# Audio_module.net
KiCad netlist of a schematic drawn in Altium Designer
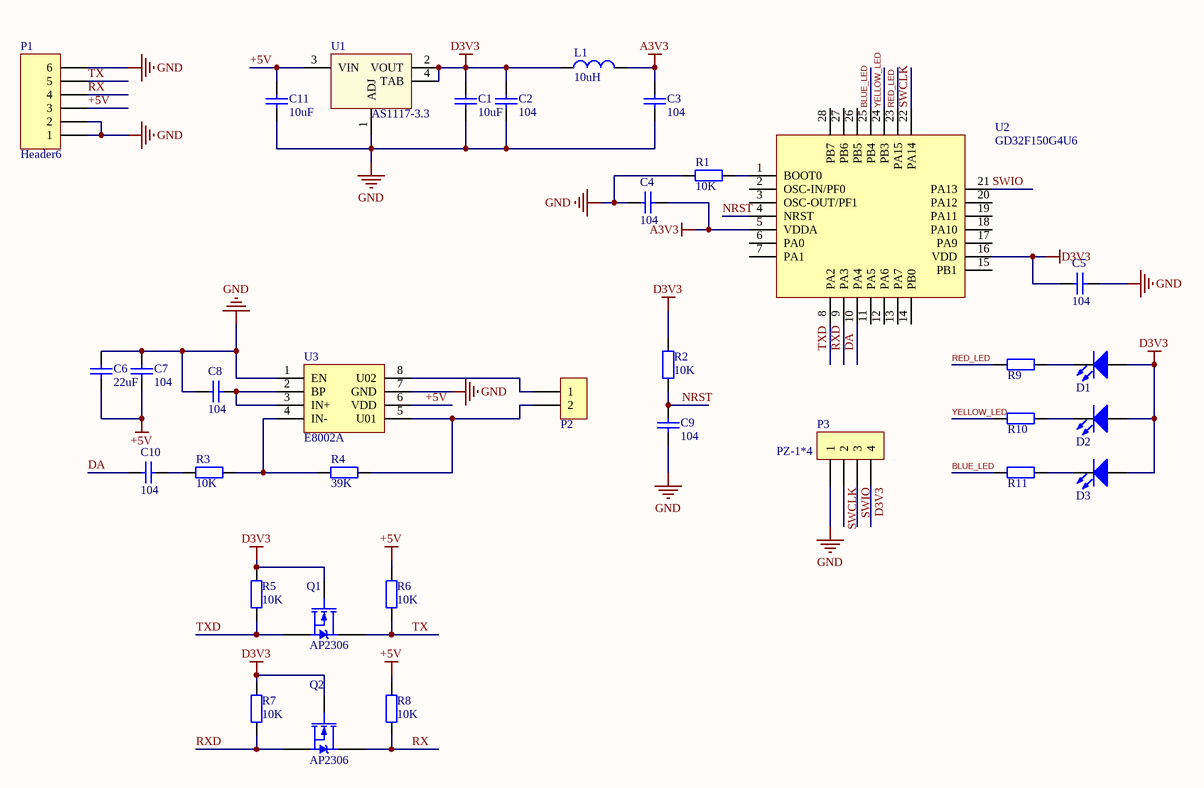
[diagram p0: Audio module.SchDoc]

(export (version "E")
  (design (tool "Eeschema 10.0.6"))
  (components
    (comp (ref "C1")
      (value "10uF")
      (footprint "0603-2")
      (description "无极性电容")
      (fields (field (name "Comment") "Cap") (field (name "PUBLISHER") "Altium Limited"))
      (libsource (lib "Audio module") (part "Cap"))
    )
    (comp (ref "C2")
      (value "104")
      (footprint "0603-2")
      (description "无极性电容")
      (fields (field (name "Comment") "Cap") (field (name "PUBLISHER") "Altium Limited"))
      (libsource (lib "Audio module") (part "Cap"))
    )
    (comp (ref "C3")
      (value "104")
      (footprint "0603-2")
      (description "无极性电容")
      (fields (field (name "Comment") "Cap") (field (name "PUBLISHER") "Altium Limited"))
      (libsource (lib "Audio module") (part "Cap"))
    )
    (comp (ref "C4")
      (value "104")
      (footprint "0603-2")
      (description "无极性电容")
      (fields (field (name "Comment") "Cap") (field (name "PUBLISHER") "Altium Limited"))
      (libsource (lib "Audio module") (part "Cap"))
    )
    (comp (ref "C5")
      (value "104")
      (footprint "0603-2")
      (description "无极性电容")
      (fields (field (name "Comment") "Cap") (field (name "PUBLISHER") "Altium Limited"))
      (libsource (lib "Audio module") (part "Cap"))
    )
    (comp (ref "C6")
      (value "22uF")
      (footprint "0603-2")
      (description "无极性电容")
      (fields (field (name "Comment") "Cap") (field (name "PUBLISHER") "Altium Limited"))
      (libsource (lib "Audio module") (part "Cap"))
    )
    (comp (ref "C7")
      (value "104")
      (footprint "0603-2")
      (description "无极性电容")
      (fields (field (name "Comment") "Cap") (field (name "PUBLISHER") "Altium Limited"))
      (libsource (lib "Audio module") (part "Cap"))
    )
    (comp (ref "C8")
      (value "104")
      (footprint "0603-2")
      (description "无极性电容")
      (fields (field (name "Comment") "Cap") (field (name "PUBLISHER") "Altium Limited"))
      (libsource (lib "Audio module") (part "Cap"))
    )
    (comp (ref "C9")
      (value "104")
      (footprint "0603-2")
      (description "无极性电容")
      (fields (field (name "Comment") "Cap") (field (name "PUBLISHER") "Altium Limited"))
      (libsource (lib "Audio module") (part "Cap"))
    )
    (comp (ref "C10")
      (value "104")
      (footprint "0603-2")
      (description "无极性电容")
      (fields (field (name "Comment") "Cap") (field (name "PUBLISHER") "Altium Limited"))
      (libsource (lib "Audio module") (part "Cap"))
    )
    (comp (ref "C11")
      (value "10uF")
      (footprint "0603-2")
      (description "无极性电容")
      (fields (field (name "Comment") "Cap") (field (name "PUBLISHER") "Altium Limited"))
      (libsource (lib "Audio module") (part "Cap"))
    )
    (comp (ref "D1") (value "RED_LED") (footprint "RES_0603") (libsource (lib "zzk") (part "LED")))
    (comp (ref "D2") (value "YELLOW_LED") (footprint "RES_0603") (libsource (lib "zzk") (part "LED")))
    (comp (ref "D3") (value "BLUE_LED") (footprint "RES_0603") (libsource (lib "zzk") (part "LED")))
    (comp (ref "L1")
      (value "10uH")
      (footprint "0805-1")
      (description "电感")
      (fields (field (name "Comment") "Inductor") (field (name "PUBLISHER") "Altium Limited"))
      (libsource (lib "Audio module") (part "Inductor"))
    )
    (comp (ref "P1")
      (value "Header6")
      (footprint "HDR6X1_A")
      (libsource (lib "Audio module") (part "Header6"))
    )
    (comp (ref "P2") (value "PZ-1*2") (footprint "HDR2X1_A") (libsource (lib "Audio module") (part "PZ-1*2")))
    (comp (ref "P3") (value "PZ-1*4") (footprint "HDR4X1_A") (libsource (lib "Audio module") (part "PZ-1*4")))
    (comp (ref "Q1")
      (value "AP2306")
      (footprint "SOT-23")
      (description "N-MOSFET1")
      (fields (field (name "PUBLISHER") "Altium Limited"))
      (libsource (lib "Audio module") (part "MOSFET-N1"))
    )
    (comp (ref "Q2")
      (value "AP2306")
      (footprint "SOT-23")
      (description "N-MOSFET1")
      (fields (field (name "PUBLISHER") "Altium Limited"))
      (libsource (lib "Audio module") (part "MOSFET-N1"))
    )
    (comp (ref "R1")
      (value "10K")
      (footprint "RES-0603")
      (description "贴片电阻")
      (fields (field (name "PUBLISHER") "Altium Limited"))
      (libsource (lib "") (part "Res1_2"))
    )
    (comp (ref "R2")
      (value "10K")
      (footprint "RES-0603")
      (description "贴片电阻")
      (fields (field (name "PUBLISHER") "Altium Limited"))
      (libsource (lib "Audio module") (part "Res1"))
    )
    (comp (ref "R3")
      (value "10K")
      (footprint "0603-1")
      (description "贴片电阻")
      (fields (field (name "Comment") "Res1") (field (name "PUBLISHER") "Altium Limited"))
      (libsource (lib "") (part "Res1_1"))
    )
    (comp (ref "R4")
      (value "39K")
      (footprint "0603-1")
      (description "贴片电阻")
      (fields (field (name "Comment") "Res1") (field (name "PUBLISHER") "Altium Limited"))
      (libsource (lib "") (part "Res1_1"))
    )
    (comp (ref "R5")
      (value "10K")
      (footprint "RES-0603")
      (description "贴片电阻")
      (fields (field (name "PUBLISHER") "Altium Limited"))
      (libsource (lib "Audio module") (part "Res1"))
    )
    (comp (ref "R6")
      (value "10K")
      (footprint "RES-0603")
      (description "贴片电阻")
      (fields (field (name "PUBLISHER") "Altium Limited"))
      (libsource (lib "Audio module") (part "Res1"))
    )
    (comp (ref "R7")
      (value "10K")
      (footprint "RES-0603")
      (description "贴片电阻")
      (fields (field (name "PUBLISHER") "Altium Limited"))
      (libsource (lib "Audio module") (part "Res1"))
    )
    (comp (ref "R8")
      (value "10K")
      (footprint "RES-0603")
      (description "贴片电阻")
      (fields (field (name "PUBLISHER") "Altium Limited"))
      (libsource (lib "Audio module") (part "Res1"))
    )
    (comp (ref "R9") (value "RES") (footprint "RES_0603") (libsource (lib "zzk") (part "RES")))
    (comp (ref "R10") (value "RES") (footprint "RES_0603") (libsource (lib "zzk") (part "RES")))
    (comp (ref "R11") (value "RES") (footprint "RES_0603") (libsource (lib "zzk") (part "RES")))
    (comp (ref "U1")
      (value "AS1117-3.3")
      (footprint "SOT-223")
      (description "AS1117")
      (libsource (lib "Audio module") (part "AS1117"))
    )
    (comp (ref "U2")
      (value "GD32F150G4U6")
      (footprint "QFN28-1")
      (libsource (lib "Audio module") (part "GD32F150G4U6"))
    )
    (comp (ref "U3") (value "E8002A") (footprint "SOP-8") (libsource (lib "Audio module") (part "E8002A")))
  )
  (nets
    (net (code "1") (name "+5V") (class "Default")
      (node (ref "C11") (pin "2") (pinfunction "2_2") (pintype "passive"))
      (node (ref "C6") (pin "2") (pinfunction "2_2") (pintype "passive"))
      (node (ref "C7") (pin "1") (pinfunction "1_1") (pintype "passive"))
      (node (ref "P1") (pin "3") (pinfunction "3_3") (pintype "passive"))
      (node (ref "R6") (pin "2") (pinfunction "2_2") (pintype "passive"))
      (node (ref "R8") (pin "2") (pinfunction "2_2") (pintype "passive"))
      (node (ref "U1") (pin "3") (pinfunction "VIN_3") (pintype "passive"))
      (node (ref "U3") (pin "6") (pinfunction "VDD_6") (pintype "passive"))
    )
    (net (code "2") (name "/BLUE_LED") (class "Default")
      (node (ref "R11") (pin "1") (pinfunction "1_1") (pintype "passive"))
      (node (ref "U2") (pin "25") (pinfunction "PB4_25") (pintype "passive"))
    )
    (net (code "3") (name "/DA") (class "Default")
      (node (ref "C10") (pin "2") (pinfunction "2_2") (pintype "passive"))
      (node (ref "U2") (pin "10") (pinfunction "PA4_10") (pintype "passive"))
    )
    (net (code "4") (name "/NRST") (class "Default")
      (node (ref "C9") (pin "2") (pinfunction "2_2") (pintype "passive"))
      (node (ref "R2") (pin "1") (pinfunction "1_1") (pintype "passive"))
      (node (ref "U2") (pin "4") (pinfunction "NRST_4") (pintype "passive"))
    )
    (net (code "5") (name "/RED_LED") (class "Default")
      (node (ref "R9") (pin "1") (pinfunction "1_1") (pintype "passive"))
      (node (ref "U2") (pin "23") (pinfunction "PA15_23") (pintype "passive"))
    )
    (net (code "6") (name "/RX") (class "Default")
      (node (ref "P1") (pin "4") (pinfunction "4_4") (pintype "passive"))
      (node (ref "Q2") (pin "3") (pinfunction "D_3") (pintype "passive"))
      (node (ref "R8") (pin "1") (pinfunction "1_1") (pintype "passive"))
    )
    (net (code "7") (name "/RXD") (class "Default")
      (node (ref "Q2") (pin "2") (pinfunction "S_2") (pintype "passive"))
      (node (ref "R7") (pin "1") (pinfunction "1_1") (pintype "passive"))
      (node (ref "U2") (pin "9") (pinfunction "PA3_9") (pintype "passive"))
    )
    (net (code "8") (name "/SWCLK") (class "Default")
      (node (ref "P3") (pin "2") (pinfunction "2_2") (pintype "passive"))
      (node (ref "U2") (pin "22") (pinfunction "PA14_22") (pintype "passive"))
    )
    (net (code "9") (name "/SWIO") (class "Default")
      (node (ref "P3") (pin "3") (pinfunction "3_3") (pintype "passive"))
      (node (ref "U2") (pin "21") (pinfunction "PA13_21") (pintype "passive"))
    )
    (net (code "10") (name "/TX") (class "Default")
      (node (ref "P1") (pin "5") (pinfunction "5_5") (pintype "passive"))
      (node (ref "Q1") (pin "3") (pinfunction "D_3") (pintype "passive"))
      (node (ref "R6") (pin "1") (pinfunction "1_1") (pintype "passive"))
    )
    (net (code "11") (name "/TXD") (class "Default")
      (node (ref "Q1") (pin "2") (pinfunction "S_2") (pintype "passive"))
      (node (ref "R5") (pin "1") (pinfunction "1_1") (pintype "passive"))
      (node (ref "U2") (pin "8") (pinfunction "PA2_8") (pintype "passive"))
    )
    (net (code "12") (name "/YELLOW_LED") (class "Default")
      (node (ref "R10") (pin "1") (pinfunction "1_1") (pintype "passive"))
      (node (ref "U2") (pin "24") (pinfunction "PB3_24") (pintype "passive"))
    )
    (net (code "13") (name "A3V3") (class "Default")
      (node (ref "C3") (pin "2") (pinfunction "2_2") (pintype "passive"))
      (node (ref "C4") (pin "1") (pinfunction "1_1") (pintype "passive"))
      (node (ref "L1") (pin "2") (pinfunction "2_2") (pintype "passive"))
      (node (ref "U2") (pin "5") (pinfunction "VDDA_5") (pintype "passive"))
    )
    (net (code "14") (name "D3V3") (class "Default")
      (node (ref "C1") (pin "2") (pinfunction "2_2") (pintype "passive"))
      (node (ref "C2") (pin "2") (pinfunction "2_2") (pintype "passive"))
      (node (ref "C5") (pin "2") (pinfunction "2_2") (pintype "passive"))
      (node (ref "D1") (pin "1") (pinfunction "A_1") (pintype "passive"))
      (node (ref "D2") (pin "1") (pinfunction "A_1") (pintype "passive"))
      (node (ref "D3") (pin "1") (pinfunction "A_1") (pintype "passive"))
      (node (ref "L1") (pin "1") (pinfunction "1_1") (pintype "passive"))
      (node (ref "P3") (pin "4") (pinfunction "4_4") (pintype "passive"))
      (node (ref "R2") (pin "2") (pinfunction "2_2") (pintype "passive"))
      (node (ref "R5") (pin "2") (pinfunction "2_2") (pintype "passive"))
      (node (ref "R7") (pin "2") (pinfunction "2_2") (pintype "passive"))
      (node (ref "U1") (pin "2") (pinfunction "VOUT_2") (pintype "passive"))
      (node (ref "U1") (pin "4") (pinfunction "TAB_4") (pintype "passive"))
      (node (ref "U2") (pin "16") (pinfunction "VDD_16") (pintype "passive"))
    )
    (net (code "15") (name "GND") (class "Default")
      (node (ref "C1") (pin "1") (pinfunction "1_1") (pintype "passive"))
      (node (ref "C11") (pin "1") (pinfunction "1_1") (pintype "passive"))
      (node (ref "C2") (pin "1") (pinfunction "1_1") (pintype "passive"))
      (node (ref "C3") (pin "1") (pinfunction "1_1") (pintype "passive"))
      (node (ref "C4") (pin "2") (pinfunction "2_2") (pintype "passive"))
      (node (ref "C5") (pin "1") (pinfunction "1_1") (pintype "passive"))
      (node (ref "C6") (pin "1") (pinfunction "1_1") (pintype "passive"))
      (node (ref "C7") (pin "2") (pinfunction "2_2") (pintype "passive"))
      (node (ref "C8") (pin "2") (pinfunction "2_2") (pintype "passive"))
      (node (ref "C9") (pin "1") (pinfunction "1_1") (pintype "passive"))
      (node (ref "P1") (pin "1") (pinfunction "1_1") (pintype "passive"))
      (node (ref "P1") (pin "2") (pinfunction "2_2") (pintype "passive"))
      (node (ref "P1") (pin "6") (pinfunction "6_6") (pintype "passive"))
      (node (ref "P3") (pin "1") (pinfunction "1_1") (pintype "passive"))
      (node (ref "R1") (pin "2") (pinfunction "2_2") (pintype "passive"))
      (node (ref "U1") (pin "1") (pinfunction "ADJ_1") (pintype "passive"))
      (node (ref "U3") (pin "1") (pinfunction "EN_1") (pintype "passive"))
      (node (ref "U3") (pin "7") (pinfunction "GND_7") (pintype "passive"))
    )
    (net (code "16") (name "Net-(C10-Pad1)") (class "Default")
      (node (ref "C10") (pin "1") (pinfunction "1_1") (pintype "passive"))
      (node (ref "R3") (pin "1") (pinfunction "1_1") (pintype "passive"))
    )
    (net (code "17") (name "Net-(D1-K)") (class "Default")
      (node (ref "D1") (pin "2") (pinfunction "K_2") (pintype "passive"))
      (node (ref "R9") (pin "2") (pinfunction "2_2") (pintype "passive"))
    )
    (net (code "18") (name "Net-(D2-K)") (class "Default")
      (node (ref "D2") (pin "2") (pinfunction "K_2") (pintype "passive"))
      (node (ref "R10") (pin "2") (pinfunction "2_2") (pintype "passive"))
    )
    (net (code "19") (name "Net-(D3-K)") (class "Default")
      (node (ref "D3") (pin "2") (pinfunction "K_2") (pintype "passive"))
      (node (ref "R11") (pin "2") (pinfunction "2_2") (pintype "passive"))
    )
    (net (code "20") (name "Net-(U2-BOOT0)") (class "Default")
      (node (ref "R1") (pin "1") (pinfunction "1_1") (pintype "passive"))
      (node (ref "U2") (pin "1") (pinfunction "BOOT0_1") (pintype "passive"))
    )
    (net (code "21") (name "Net-(U3-BP)") (class "Default")
      (node (ref "C8") (pin "1") (pinfunction "1_1") (pintype "passive"))
      (node (ref "U3") (pin "2") (pinfunction "BP_2") (pintype "passive"))
      (node (ref "U3") (pin "3") (pinfunction "IN+_3") (pintype "passive"))
    )
    (net (code "22") (name "Net-(U3-IN-)") (class "Default")
      (node (ref "R3") (pin "2") (pinfunction "2_2") (pintype "passive"))
      (node (ref "R4") (pin "1") (pinfunction "1_1") (pintype "passive"))
      (node (ref "U3") (pin "4") (pinfunction "IN-_4") (pintype "passive"))
    )
    (net (code "23") (name "Net-(U3-U01)") (class "Default")
      (node (ref "P2") (pin "2") (pinfunction "2_2") (pintype "passive"))
      (node (ref "R4") (pin "2") (pinfunction "2_2") (pintype "passive"))
      (node (ref "U3") (pin "5") (pinfunction "U01_5") (pintype "passive"))
    )
    (net (code "24") (name "Net-(U3-U02)") (class "Default")
      (node (ref "P2") (pin "1") (pinfunction "1_1") (pintype "passive"))
      (node (ref "U3") (pin "8") (pinfunction "U02_8") (pintype "passive"))
    )
    (net (code "25") (name "unconnected-(Q1-1-PadG)") (class "Default")
      (node (ref "Q1") (pin "G") (pinfunction "1_G") (pintype "passive"))
    )
    (net (code "26") (name "unconnected-(Q2-1-PadG)") (class "Default")
      (node (ref "Q2") (pin "G") (pinfunction "1_G") (pintype "passive"))
    )
    (net (code "27") (name "unconnected-(U2-OSC-IN{slash}PF0-Pad2)") (class "Default")
      (node (ref "U2") (pin "2") (pinfunction "OSC-IN/PF0_2") (pintype "passive"))
    )
    (net (code "28") (name "unconnected-(U2-OSC-OUT{slash}PF1-Pad3)") (class "Default")
      (node (ref "U2") (pin "3") (pinfunction "OSC-OUT/PF1_3") (pintype "passive"))
    )
    (net (code "29") (name "unconnected-(U2-PA0-Pad6)") (class "Default")
      (node (ref "U2") (pin "6") (pinfunction "PA0_6") (pintype "passive"))
    )
    (net (code "30") (name "unconnected-(U2-PA1-Pad7)") (class "Default")
      (node (ref "U2") (pin "7") (pinfunction "PA1_7") (pintype "passive"))
    )
    (net (code "31") (name "unconnected-(U2-PA5-Pad11)") (class "Default")
      (node (ref "U2") (pin "11") (pinfunction "PA5_11") (pintype "passive"))
    )
    (net (code "32") (name "unconnected-(U2-PA6-Pad12)") (class "Default")
      (node (ref "U2") (pin "12") (pinfunction "PA6_12") (pintype "passive"))
    )
    (net (code "33") (name "unconnected-(U2-PA7-Pad13)") (class "Default")
      (node (ref "U2") (pin "13") (pinfunction "PA7_13") (pintype "passive"))
    )
    (net (code "34") (name "unconnected-(U2-PA9-Pad17)") (class "Default")
      (node (ref "U2") (pin "17") (pinfunction "PA9_17") (pintype "passive"))
    )
    (net (code "35") (name "unconnected-(U2-PA10-Pad18)") (class "Default")
      (node (ref "U2") (pin "18") (pinfunction "PA10_18") (pintype "passive"))
    )
    (net (code "36") (name "unconnected-(U2-PA11-Pad19)") (class "Default")
      (node (ref "U2") (pin "19") (pinfunction "PA11_19") (pintype "passive"))
    )
    (net (code "37") (name "unconnected-(U2-PA12-Pad20)") (class "Default")
      (node (ref "U2") (pin "20") (pinfunction "PA12_20") (pintype "passive"))
    )
    (net (code "38") (name "unconnected-(U2-PB0-Pad14)") (class "Default")
      (node (ref "U2") (pin "14") (pinfunction "PB0_14") (pintype "passive"))
    )
    (net (code "39") (name "unconnected-(U2-PB1-Pad15)") (class "Default")
      (node (ref "U2") (pin "15") (pinfunction "PB1_15") (pintype "passive"))
    )
    (net (code "40") (name "unconnected-(U2-PB5-Pad26)") (class "Default")
      (node (ref "U2") (pin "26") (pinfunction "PB5_26") (pintype "passive"))
    )
    (net (code "41") (name "unconnected-(U2-PB6-Pad27)") (class "Default")
      (node (ref "U2") (pin "27") (pinfunction "PB6_27") (pintype "passive"))
    )
    (net (code "42") (name "unconnected-(U2-PB7-Pad28)") (class "Default")
      (node (ref "U2") (pin "28") (pinfunction "PB7_28") (pintype "passive"))
    )
  )
)
